# Power.net
KiCad netlist of a schematic drawn in Altium Designer
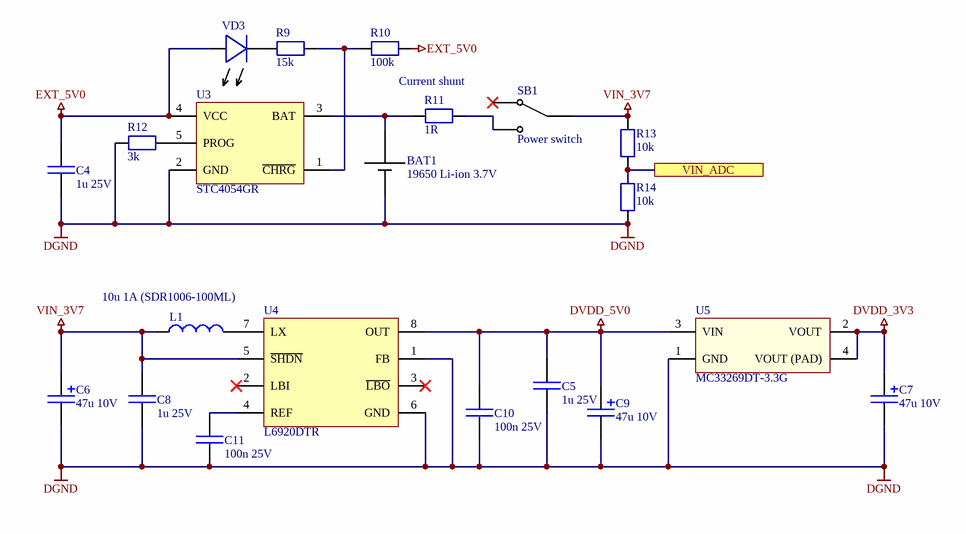
[diagram p0: Power.SchDoc]

(export (version "E")
  (design (tool "Eeschema 10.0.6"))
  (components
    (comp (ref "BAT1")
      (value "19650 Li-ion 3.7V")
      (footprint "PLS-2 2.54")
      (description "Battery")
      (libsource (lib "power") (part "Battery"))
    )
    (comp (ref "C4")
      (value "1u 25V")
      (footprint "C_0603/1608")
      (description "Non-polarized capacitor")
      (libsource (lib "passive") (part "Capacitor"))
    )
    (comp (ref "C5")
      (value "1u 25V")
      (footprint "C_0603/1608")
      (description "Non-polarized capacitor")
      (libsource (lib "passive") (part "Capacitor"))
    )
    (comp (ref "C6")
      (value "47u 10V")
      (footprint "TECAP_TYPE_B")
      (description "Polarized capacitor")
      (libsource (lib "passive") (part "Capacitor polar"))
    )
    (comp (ref "C7")
      (value "47u 10V")
      (footprint "TECAP_TYPE_B")
      (description "Polarized capacitor")
      (libsource (lib "passive") (part "Capacitor polar"))
    )
    (comp (ref "C8")
      (value "1u 25V")
      (footprint "C_0603/1608")
      (description "Non-polarized capacitor")
      (libsource (lib "passive") (part "Capacitor"))
    )
    (comp (ref "C9")
      (value "47u 10V")
      (footprint "TECAP_TYPE_B")
      (description "Polarized capacitor")
      (libsource (lib "passive") (part "Capacitor polar"))
    )
    (comp (ref "C10")
      (value "100n 25V")
      (footprint "C_0603/1608")
      (description "Non-polarized capacitor")
      (libsource (lib "passive") (part "Capacitor"))
    )
    (comp (ref "C11")
      (value "100n 25V")
      (footprint "C_0603/1608")
      (description "Non-polarized capacitor")
      (libsource (lib "passive") (part "Capacitor"))
    )
    (comp (ref "L1")
      (value "10u 1A (SDR1006-100ML)")
      (footprint "L_1006")
      (description "Inductor")
      (libsource (lib "passive") (part "Inductor"))
    )
    (comp (ref "R9")
      (value "15k")
      (footprint "R_0603/1608")
      (description "Resistor")
      (libsource (lib "passive") (part "Resistor"))
    )
    (comp (ref "R10")
      (value "100k")
      (footprint "R_0603/1608")
      (description "Resistor")
      (libsource (lib "passive") (part "Resistor"))
    )
    (comp (ref "R11")
      (value "1R")
      (footprint "R_0603/1608")
      (description "Resistor")
      (libsource (lib "passive") (part "Resistor"))
    )
    (comp (ref "R12")
      (value "3k")
      (footprint "R_0603/1608")
      (description "Resistor")
      (libsource (lib "passive") (part "Resistor"))
    )
    (comp (ref "R13")
      (value "10k")
      (footprint "R_0603/1608")
      (description "Resistor")
      (libsource (lib "passive") (part "Resistor"))
    )
    (comp (ref "R14")
      (value "10k")
      (footprint "R_0603/1608")
      (description "Resistor")
      (libsource (lib "passive") (part "Resistor"))
    )
    (comp (ref "SB1")
      (value "Power switch")
      (footprint "KBB40_2P2W")
      (description "Switch 3-pin")
      (libsource (lib "controls") (part "Switch 3-pin"))
    )
    (comp (ref "U3")
      (value "STC4054GR")
      (footprint "SOT23-5")
      (description "Li-ion charger")
      (libsource (lib "power") (part "STC4054GR"))
    )
    (comp (ref "U4")
      (value "L6920DTR")
      (footprint "SO8_0.65")
      (description "DC-DC step-up switching regulator")
      (libsource (lib "power") (part "L6920DTR"))
    )
    (comp (ref "U5")
      (value "MC33269DT-3.3G")
      (footprint "TO252AA/DPAK")
      (description "LDO voltage regulator")
      (libsource (lib "power") (part "LM1117"))
    )
    (comp (ref "VD3")
      (value "~")
      (footprint "PLS-2 2.54")
      (description "LED")
      (libsource (lib "indication") (part "LED"))
    )
  )
  (nets
    (net (code "1") (name "/VIN_ADC") (class "Default")
      (node (ref "R13") (pin "1") (pintype "passive"))
      (node (ref "R14") (pin "2") (pintype "passive"))
    )
    (net (code "2") (name "DGND") (class "Default")
      (node (ref "BAT1") (pin "1") (pintype "power_in"))
      (node (ref "C10") (pin "2") (pintype "passive"))
      (node (ref "C11") (pin "2") (pintype "passive"))
      (node (ref "C4") (pin "2") (pintype "passive"))
      (node (ref "C5") (pin "2") (pintype "passive"))
      (node (ref "C6") (pin "2") (pinfunction "NEG_2") (pintype "passive"))
      (node (ref "C7") (pin "2") (pinfunction "NEG_2") (pintype "passive"))
      (node (ref "C8") (pin "2") (pintype "passive"))
      (node (ref "C9") (pin "2") (pinfunction "NEG_2") (pintype "passive"))
      (node (ref "R12") (pin "2") (pintype "passive"))
      (node (ref "R14") (pin "1") (pintype "passive"))
      (node (ref "U3") (pin "2") (pinfunction "GND_2") (pintype "passive"))
      (node (ref "U4") (pin "1") (pinfunction "FB_1") (pintype "passive"))
      (node (ref "U4") (pin "6") (pinfunction "GND_6") (pintype "passive"))
      (node (ref "U5") (pin "1") (pinfunction "GND_1") (pintype "power_in"))
    )
    (net (code "3") (name "DVDD_3V3") (class "Default")
      (node (ref "C7") (pin "1") (pinfunction "POS_1") (pintype "passive"))
      (node (ref "U5") (pin "2") (pinfunction "VOUT_2") (pintype "power_in"))
      (node (ref "U5") (pin "4") (pinfunction "VOUT_(PAD)_4") (pintype "power_in"))
    )
    (net (code "4") (name "DVDD_5V0") (class "Default")
      (node (ref "C10") (pin "1") (pintype "passive"))
      (node (ref "C5") (pin "1") (pintype "passive"))
      (node (ref "C9") (pin "1") (pinfunction "POS_1") (pintype "passive"))
      (node (ref "U4") (pin "8") (pinfunction "OUT_8") (pintype "passive"))
      (node (ref "U5") (pin "3") (pinfunction "VIN_3") (pintype "power_in"))
    )
    (net (code "5") (name "EXT_5V0") (class "Default")
      (node (ref "C4") (pin "1") (pintype "passive"))
      (node (ref "R10") (pin "2") (pintype "passive"))
      (node (ref "U3") (pin "4") (pinfunction "VCC_4") (pintype "passive"))
      (node (ref "VD3") (pin "A") (pinfunction "A_A") (pintype "passive"))
    )
    (net (code "6") (name "Net-(R9-Pad2)") (class "Default")
      (node (ref "R9") (pin "2") (pintype "passive"))
      (node (ref "VD3") (pin "C") (pinfunction "C_C") (pintype "passive"))
    )
    (net (code "7") (name "Net-(R11-Pad1)") (class "Default")
      (node (ref "R11") (pin "1") (pintype "passive"))
      (node (ref "SB1") (pin "3") (pinfunction "3_3") (pintype "passive"))
    )
    (net (code "8") (name "Net-(U3-BAT)") (class "Default")
      (node (ref "BAT1") (pin "2") (pintype "power_in"))
      (node (ref "R11") (pin "2") (pintype "passive"))
      (node (ref "U3") (pin "3") (pinfunction "BAT_3") (pintype "passive"))
    )
    (net (code "9") (name "Net-(U3-PROG)") (class "Default")
      (node (ref "R12") (pin "1") (pintype "passive"))
      (node (ref "U3") (pin "5") (pinfunction "PROG_5") (pintype "passive"))
    )
    (net (code "10") (name "Net-(U3-~{CHRG})") (class "Default")
      (node (ref "R10") (pin "1") (pintype "passive"))
      (node (ref "R9") (pin "1") (pintype "passive"))
      (node (ref "U3") (pin "1") (pinfunction "~{CHRG}_1") (pintype "passive"))
    )
    (net (code "11") (name "Net-(U4-LX)") (class "Default")
      (node (ref "L1") (pin "2") (pintype "passive"))
      (node (ref "U4") (pin "7") (pinfunction "LX_7") (pintype "passive"))
    )
    (net (code "12") (name "Net-(U4-REF)") (class "Default")
      (node (ref "C11") (pin "1") (pintype "passive"))
      (node (ref "U4") (pin "4") (pinfunction "REF_4") (pintype "passive"))
    )
    (net (code "13") (name "VIN_3V7") (class "Default")
      (node (ref "C6") (pin "1") (pinfunction "POS_1") (pintype "passive"))
      (node (ref "C8") (pin "1") (pintype "passive"))
      (node (ref "L1") (pin "1") (pintype "passive"))
      (node (ref "R13") (pin "2") (pintype "passive"))
      (node (ref "SB1") (pin "1") (pinfunction "1_1") (pintype "passive"))
      (node (ref "U4") (pin "5") (pinfunction "~{SHDN}_5") (pintype "passive"))
    )
    (net (code "14") (name "unconnected-(SB1-Pad2)") (class "Default")
      (node (ref "SB1") (pin "2") (pinfunction "2_2") (pintype "passive+no_connect"))
    )
    (net (code "15") (name "unconnected-(U4-LBI-Pad2)") (class "Default")
      (node (ref "U4") (pin "2") (pinfunction "LBI_2") (pintype "passive+no_connect"))
    )
    (net (code "16") (name "unconnected-(U4-~{LBO}-Pad3)") (class "Default")
      (node (ref "U4") (pin "3") (pinfunction "~{LBO}_3") (pintype "passive+no_connect"))
    )
  )
)
